# Screens.net
KiCad netlist of a schematic drawn in Altium Designer
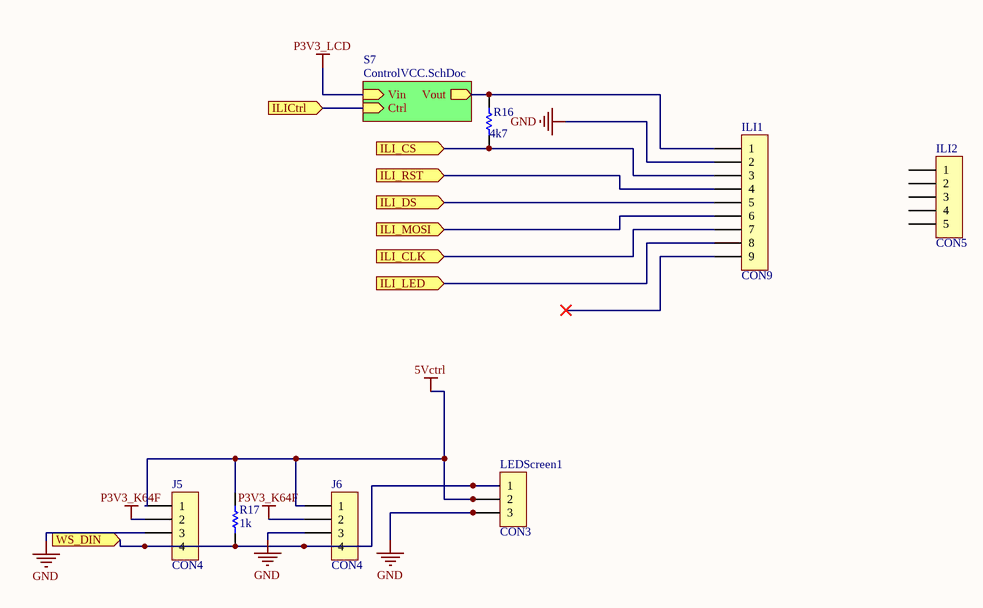
[diagram p0: Screens.SchDoc]

(export (version "E")
  (design (tool "Eeschema 10.0.6"))
  (components
    (comp (ref "ILI1") (value "CON9") (footprint "SIP9") (libsource (lib "LIBEBAL") (part "CON9")))
    (comp (ref "ILI2") (value "CON5") (footprint "SIP5") (libsource (lib "LIBEBAL") (part "CON5")))
    (comp (ref "J5") (value "CON4") (footprint "SIP4") (libsource (lib "LIBEBAL") (part "CON4")))
    (comp (ref "J6") (value "CON4") (footprint "SIP4") (libsource (lib "LIBEBAL") (part "CON4")))
    (comp (ref "LEDScreen1") (value "CON3") (footprint "SIP3") (libsource (lib "LIBEBAL") (part "CON3")))
    (comp (ref "R16") (value "4k7") (footprint "0805") (libsource (lib "LIBEBAL") (part "RES")))
    (comp (ref "R17") (value "1k") (footprint "0805") (libsource (lib "LIBEBAL") (part "RES")))
  )
  (nets
    (net (code "2") (name "/ILI_CLK") (class "Default")
      (node (ref "ILI1") (pin "7") (pinfunction "7_7") (pintype "passive"))
    )
    (net (code "3") (name "/ILI_CS") (class "Default")
      (node (ref "ILI1") (pin "3") (pinfunction "3_3") (pintype "passive"))
      (node (ref "R16") (pin "1") (pinfunction "1_1") (pintype "passive"))
    )
    (net (code "4") (name "/ILI_DS") (class "Default")
      (node (ref "ILI1") (pin "5") (pinfunction "5_5") (pintype "passive"))
    )
    (net (code "5") (name "/ILI_LED") (class "Default")
      (node (ref "ILI1") (pin "8") (pinfunction "8_8") (pintype "passive"))
    )
    (net (code "6") (name "/ILI_MOSI") (class "Default")
      (node (ref "ILI1") (pin "6") (pinfunction "6_6") (pintype "passive"))
    )
    (net (code "7") (name "/ILI_RST") (class "Default")
      (node (ref "ILI1") (pin "4") (pinfunction "4_4") (pintype "passive"))
    )
    (net (code "8") (name "/Vout") (class "Default")
      (node (ref "ILI1") (pin "1") (pinfunction "1_1") (pintype "passive"))
      (node (ref "R16") (pin "2") (pinfunction "2_2") (pintype "passive"))
    )
    (net (code "9") (name "/WS_DIN") (class "Default")
      (node (ref "J5") (pin "4") (pinfunction "4_4") (pintype "passive"))
      (node (ref "J6") (pin "4") (pinfunction "4_4") (pintype "passive"))
      (node (ref "LEDScreen1") (pin "1") (pinfunction "1_1") (pintype "passive"))
      (node (ref "R17") (pin "1") (pinfunction "1_1") (pintype "passive"))
    )
    (net (code "10") (name "5Vctrl") (class "Default")
      (node (ref "J5") (pin "1") (pinfunction "1_1") (pintype "passive"))
      (node (ref "J6") (pin "1") (pinfunction "1_1") (pintype "passive"))
      (node (ref "LEDScreen1") (pin "2") (pinfunction "2_2") (pintype "passive"))
      (node (ref "R17") (pin "2") (pinfunction "2_2") (pintype "passive"))
    )
    (net (code "11") (name "GND") (class "Default")
      (node (ref "ILI1") (pin "2") (pinfunction "2_2") (pintype "passive"))
      (node (ref "J5") (pin "3") (pinfunction "3_3") (pintype "passive"))
      (node (ref "J6") (pin "3") (pinfunction "3_3") (pintype "passive"))
      (node (ref "LEDScreen1") (pin "3") (pinfunction "3_3") (pintype "passive"))
    )
    (net (code "12") (name "P3V3_K64F") (class "Default")
      (node (ref "J5") (pin "2") (pinfunction "2_2") (pintype "passive"))
      (node (ref "J6") (pin "2") (pinfunction "2_2") (pintype "passive"))
    )
    (net (code "14") (name "unconnected-(ILI1-Pad9)") (class "Default")
      (node (ref "ILI1") (pin "9") (pinfunction "9_9") (pintype "passive+no_connect"))
    )
    (net (code "15") (name "unconnected-(ILI2-Pad1)") (class "Default")
      (node (ref "ILI2") (pin "1") (pinfunction "1_1") (pintype "passive"))
    )
    (net (code "16") (name "unconnected-(ILI2-Pad2)") (class "Default")
      (node (ref "ILI2") (pin "2") (pinfunction "2_2") (pintype "passive"))
    )
    (net (code "17") (name "unconnected-(ILI2-Pad3)") (class "Default")
      (node (ref "ILI2") (pin "3") (pinfunction "3_3") (pintype "passive"))
    )
    (net (code "18") (name "unconnected-(ILI2-Pad4)") (class "Default")
      (node (ref "ILI2") (pin "4") (pinfunction "4_4") (pintype "passive"))
    )
    (net (code "19") (name "unconnected-(ILI2-Pad5)") (class "Default")
      (node (ref "ILI2") (pin "5") (pinfunction "5_5") (pintype "passive"))
    )
  )
)
